# flash_adc.net
KiCad netlist of a schematic drawn in EAGLE
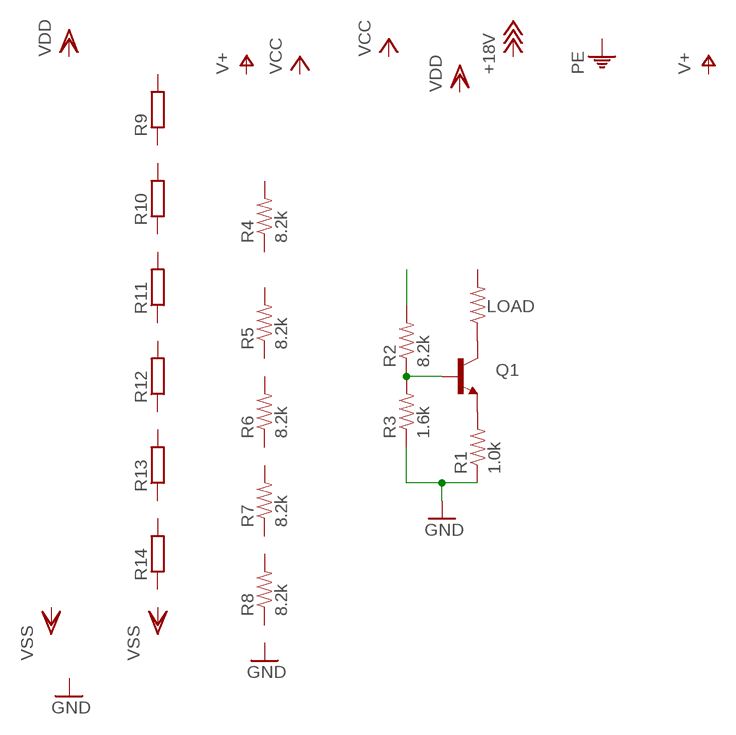
[diagram p0: schematic, sheet 1]

(export (version "E")
  (design (tool "Eeschema 10.0.6"))
  (components
    (comp (ref "LOAD")
      (value "RESISTOR0402-RES")
      (footprint "eagle-import:0402-RES")
      (libsource (lib "eagle-import") (part "RESISTOR0402-RES"))
    )
    (comp (ref "Q1")
      (value "TRANSISTOR_NPN\"")
      (footprint "eagle-import:SOT223")
      (libsource (lib "eagle-import") (part "TRANSISTOR_NPN{dblquote}"))
    )
    (comp (ref "R1")
      (value "1.0k")
      (footprint "eagle-import:0402-RES")
      (libsource (lib "eagle-import") (part "RESISTOR0402-RES"))
    )
    (comp (ref "R2")
      (value "8.2k")
      (footprint "eagle-import:0402-RES")
      (libsource (lib "eagle-import") (part "RESISTOR0402-RES"))
    )
    (comp (ref "R3")
      (value "1.6k")
      (footprint "eagle-import:0402-RES")
      (libsource (lib "eagle-import") (part "RESISTOR0402-RES"))
    )
    (comp (ref "R4")
      (value "8.2k")
      (footprint "eagle-import:0402-RES")
      (libsource (lib "eagle-import") (part "RESISTOR0402-RES"))
    )
    (comp (ref "R5")
      (value "8.2k")
      (footprint "eagle-import:0402-RES")
      (libsource (lib "eagle-import") (part "RESISTOR0402-RES"))
    )
    (comp (ref "R6")
      (value "8.2k")
      (footprint "eagle-import:0402-RES")
      (libsource (lib "eagle-import") (part "RESISTOR0402-RES"))
    )
    (comp (ref "R7")
      (value "8.2k")
      (footprint "eagle-import:0402-RES")
      (libsource (lib "eagle-import") (part "RESISTOR0402-RES"))
    )
    (comp (ref "R8")
      (value "8.2k")
      (footprint "eagle-import:0402-RES")
      (libsource (lib "eagle-import") (part "RESISTOR0402-RES"))
    )
    (comp (ref "R9")
      (value "R-EU_R0805")
      (footprint "eagle-import:R0805")
      (libsource (lib "eagle-import") (part "R-EU_R0805"))
    )
    (comp (ref "R10")
      (value "R-EU_R0805")
      (footprint "eagle-import:R0805")
      (libsource (lib "eagle-import") (part "R-EU_R0805"))
    )
    (comp (ref "R11")
      (value "R-EU_R0805")
      (footprint "eagle-import:R0805")
      (libsource (lib "eagle-import") (part "R-EU_R0805"))
    )
    (comp (ref "R12")
      (value "R-EU_R0805")
      (footprint "eagle-import:R0805")
      (libsource (lib "eagle-import") (part "R-EU_R0805"))
    )
    (comp (ref "R13")
      (value "R-EU_R0805")
      (footprint "eagle-import:R0805")
      (libsource (lib "eagle-import") (part "R-EU_R0805"))
    )
    (comp (ref "R14")
      (value "R-EU_R0805")
      (footprint "eagle-import:R0805")
      (libsource (lib "eagle-import") (part "R-EU_R0805"))
    )
  )
  (nets
    (net (code "2") (name "GND") (class "Default")
      (node (ref "R1") (pin "1") (pinfunction "1_1") (pintype "passive"))
      (node (ref "R3") (pin "1") (pinfunction "1_1") (pintype "passive"))
    )
    (net (code "3") (name "Net-(Q1-B)") (class "Default")
      (node (ref "Q1") (pin "1") (pinfunction "B_1") (pintype "passive"))
      (node (ref "R2") (pin "1") (pinfunction "1_1") (pintype "passive"))
      (node (ref "R3") (pin "2") (pinfunction "2_2") (pintype "passive"))
    )
    (net (code "4") (name "Net-(Q1-C)") (class "Default")
      (node (ref "LOAD") (pin "1") (pinfunction "1_1") (pintype "passive"))
      (node (ref "Q1") (pin "2") (pinfunction "C_2") (pintype "passive"))
    )
    (net (code "5") (name "Net-(Q1-E)") (class "Default")
      (node (ref "Q1") (pin "3") (pinfunction "E_3") (pintype "passive"))
      (node (ref "R1") (pin "2") (pinfunction "2_2") (pintype "passive"))
    )
    (net (code "11") (name "unconnected-(LOAD-Pad2)") (class "Default")
      (node (ref "LOAD") (pin "2") (pinfunction "2_2") (pintype "passive"))
    )
    (net (code "12") (name "unconnected-(R2-Pad2)") (class "Default")
      (node (ref "R2") (pin "2") (pinfunction "2_2") (pintype "passive"))
    )
    (net (code "13") (name "unconnected-(R4-Pad1)") (class "Default")
      (node (ref "R4") (pin "1") (pinfunction "1_1") (pintype "passive"))
    )
    (net (code "14") (name "unconnected-(R4-Pad2)") (class "Default")
      (node (ref "R4") (pin "2") (pinfunction "2_2") (pintype "passive"))
    )
    (net (code "15") (name "unconnected-(R5-Pad1)") (class "Default")
      (node (ref "R5") (pin "1") (pinfunction "1_1") (pintype "passive"))
    )
    (net (code "16") (name "unconnected-(R5-Pad2)") (class "Default")
      (node (ref "R5") (pin "2") (pinfunction "2_2") (pintype "passive"))
    )
    (net (code "17") (name "unconnected-(R6-Pad1)") (class "Default")
      (node (ref "R6") (pin "1") (pinfunction "1_1") (pintype "passive"))
    )
    (net (code "18") (name "unconnected-(R6-Pad2)") (class "Default")
      (node (ref "R6") (pin "2") (pinfunction "2_2") (pintype "passive"))
    )
    (net (code "19") (name "unconnected-(R7-Pad1)") (class "Default")
      (node (ref "R7") (pin "1") (pinfunction "1_1") (pintype "passive"))
    )
    (net (code "20") (name "unconnected-(R7-Pad2)") (class "Default")
      (node (ref "R7") (pin "2") (pinfunction "2_2") (pintype "passive"))
    )
    (net (code "21") (name "unconnected-(R8-Pad1)") (class "Default")
      (node (ref "R8") (pin "1") (pinfunction "1_1") (pintype "passive"))
    )
    (net (code "22") (name "unconnected-(R8-Pad2)") (class "Default")
      (node (ref "R8") (pin "2") (pinfunction "2_2") (pintype "passive"))
    )
    (net (code "23") (name "unconnected-(R9-Pad1)") (class "Default")
      (node (ref "R9") (pin "1") (pinfunction "1_1") (pintype "passive"))
    )
    (net (code "24") (name "unconnected-(R9-Pad2)") (class "Default")
      (node (ref "R9") (pin "2") (pinfunction "2_2") (pintype "passive"))
    )
    (net (code "25") (name "unconnected-(R10-Pad1)") (class "Default")
      (node (ref "R10") (pin "1") (pinfunction "1_1") (pintype "passive"))
    )
    (net (code "26") (name "unconnected-(R10-Pad2)") (class "Default")
      (node (ref "R10") (pin "2") (pinfunction "2_2") (pintype "passive"))
    )
    (net (code "27") (name "unconnected-(R11-Pad1)") (class "Default")
      (node (ref "R11") (pin "1") (pinfunction "1_1") (pintype "passive"))
    )
    (net (code "28") (name "unconnected-(R11-Pad2)") (class "Default")
      (node (ref "R11") (pin "2") (pinfunction "2_2") (pintype "passive"))
    )
    (net (code "29") (name "unconnected-(R12-Pad1)") (class "Default")
      (node (ref "R12") (pin "1") (pinfunction "1_1") (pintype "passive"))
    )
    (net (code "30") (name "unconnected-(R12-Pad2)") (class "Default")
      (node (ref "R12") (pin "2") (pinfunction "2_2") (pintype "passive"))
    )
    (net (code "31") (name "unconnected-(R13-Pad1)") (class "Default")
      (node (ref "R13") (pin "1") (pinfunction "1_1") (pintype "passive"))
    )
    (net (code "32") (name "unconnected-(R13-Pad2)") (class "Default")
      (node (ref "R13") (pin "2") (pinfunction "2_2") (pintype "passive"))
    )
    (net (code "33") (name "unconnected-(R14-Pad1)") (class "Default")
      (node (ref "R14") (pin "1") (pinfunction "1_1") (pintype "passive"))
    )
    (net (code "34") (name "unconnected-(R14-Pad2)") (class "Default")
      (node (ref "R14") (pin "2") (pinfunction "2_2") (pintype "passive"))
    )
  )
)
